# Frequency_synthesizer_v1_1.net
KiCad netlist of a schematic drawn in EAGLE
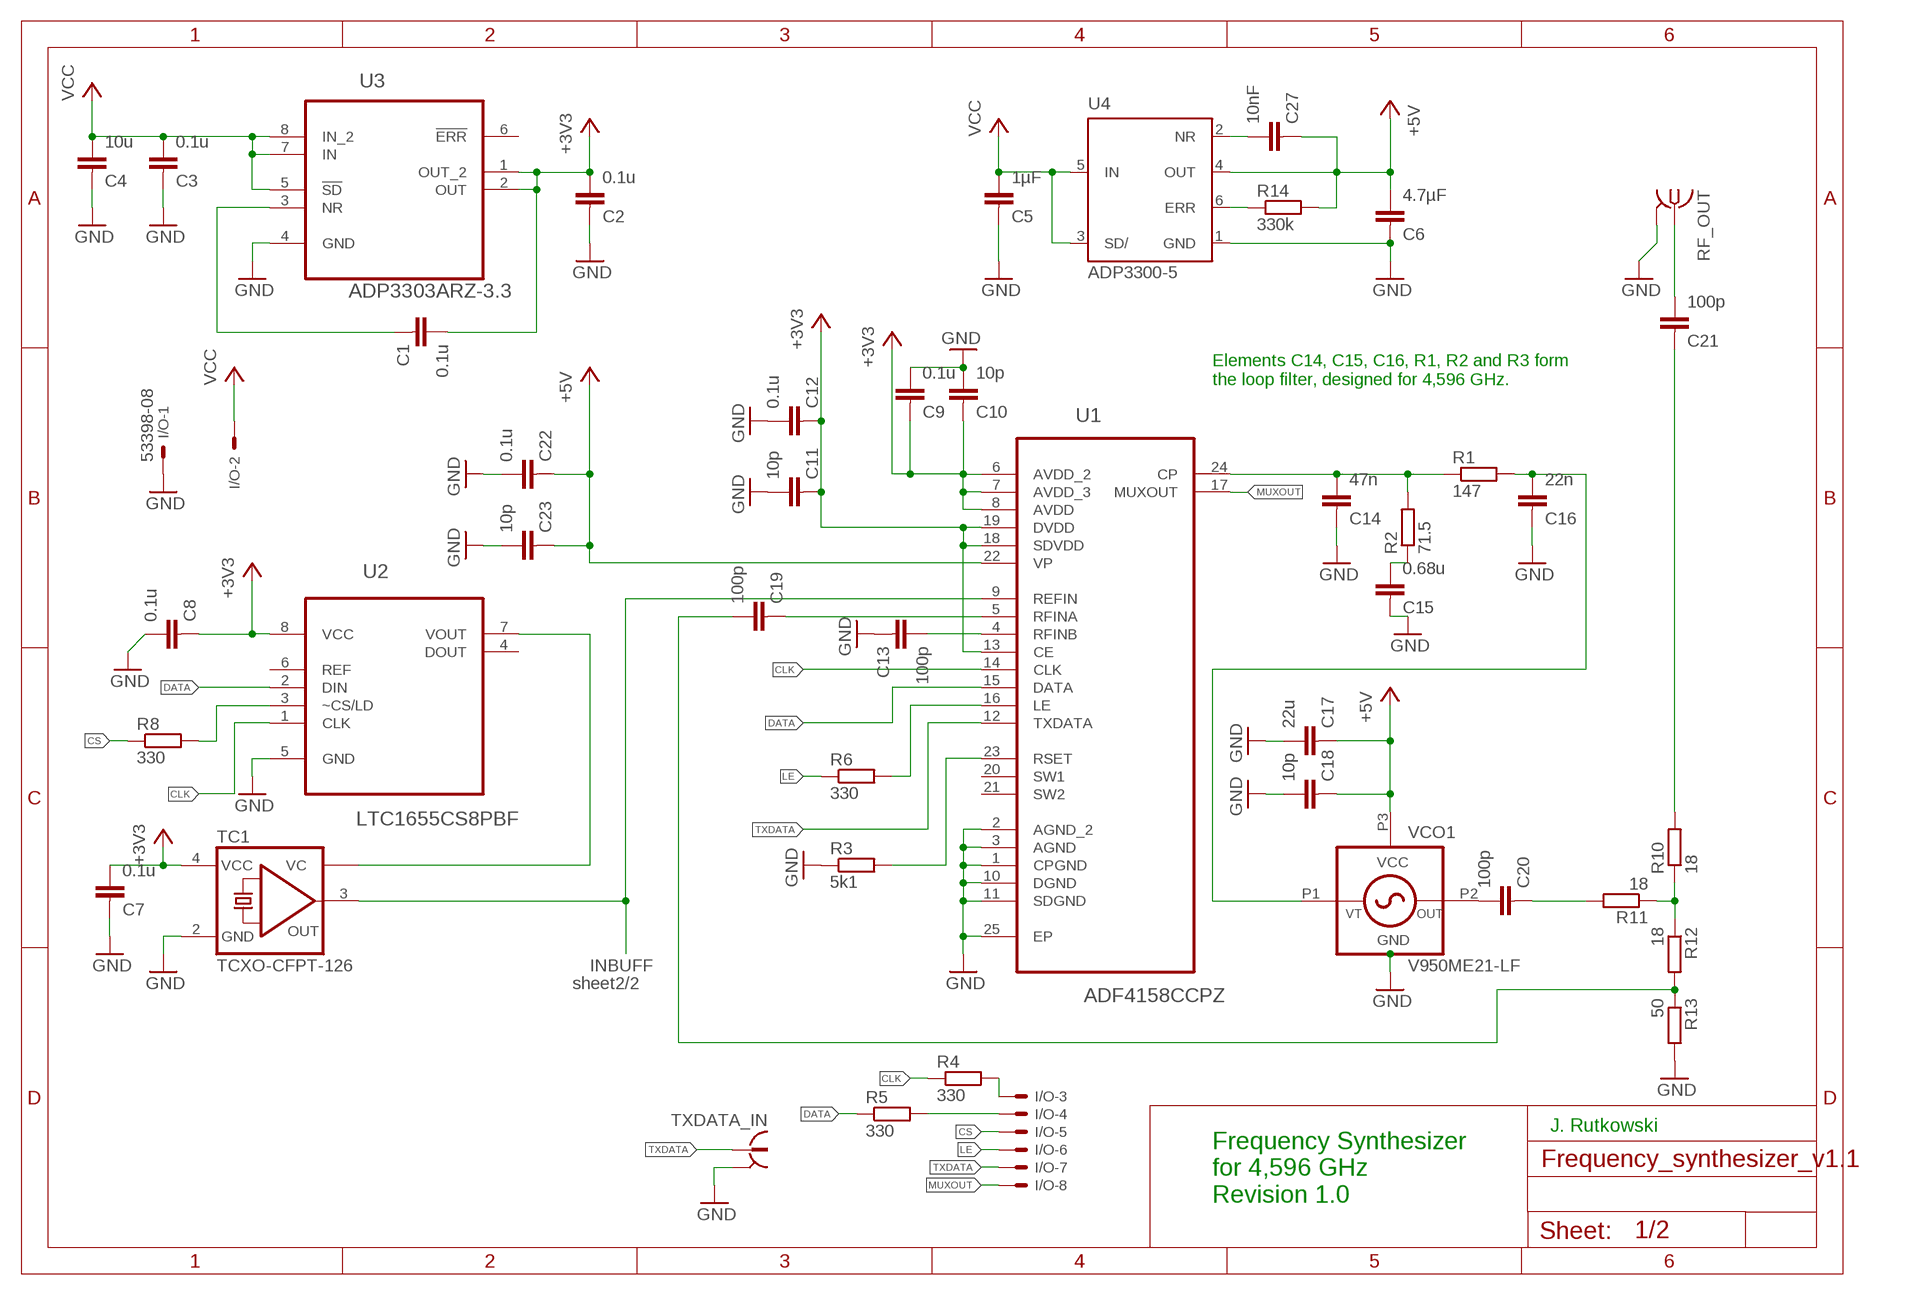
[diagram p0: schematic, sheet 1]
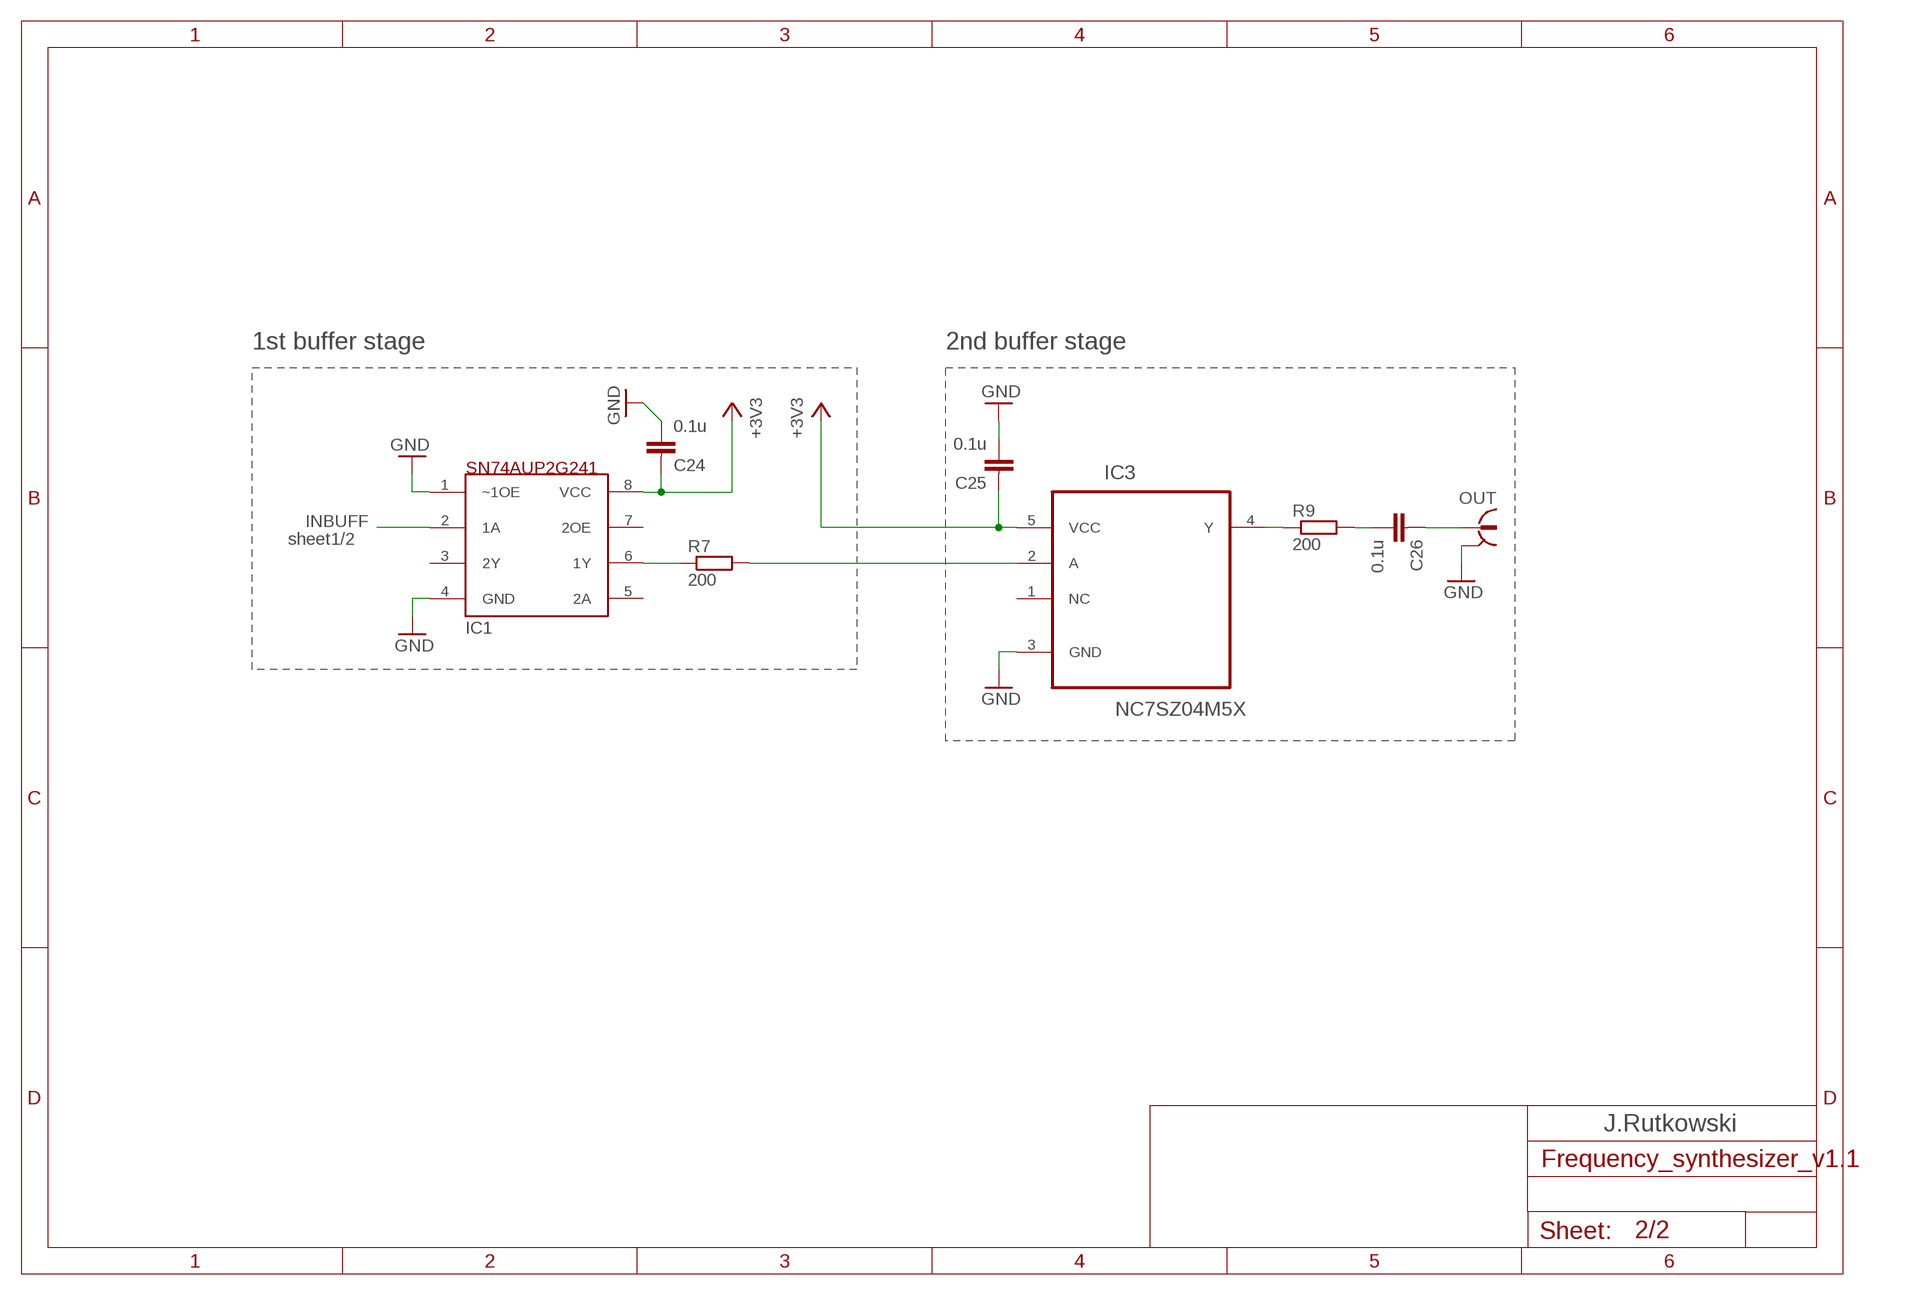
[diagram p1: schematic, sheet 2]

(export (version "E")
  (design (tool "Eeschema 10.0.6"))
  (components
    (comp (ref "C1")
      (value "0.1u")
      (footprint "eagle-import:C0603K")
      (libsource (lib "eagle-import") (part "C-EUC0603K"))
    )
    (comp (ref "C2")
      (value "0.1u")
      (footprint "eagle-import:C0603K")
      (libsource (lib "eagle-import") (part "C-EUC0603K"))
    )
    (comp (ref "C3")
      (value "0.1u")
      (footprint "eagle-import:C0603K")
      (libsource (lib "eagle-import") (part "C-EUC0603K"))
    )
    (comp (ref "C4")
      (value "10u")
      (footprint "eagle-import:C0805K")
      (libsource (lib "eagle-import") (part "C-EUC0805K"))
    )
    (comp (ref "C5")
      (value "1µF")
      (footprint "eagle-import:C0603K")
      (libsource (lib "eagle-import") (part "C-EUC0603K"))
    )
    (comp (ref "C6")
      (value "4.7µF")
      (footprint "eagle-import:C0603K")
      (libsource (lib "eagle-import") (part "C-EUC0603K"))
    )
    (comp (ref "C7")
      (value "0.1u")
      (footprint "eagle-import:C0603K")
      (libsource (lib "eagle-import") (part "C-EUC0603K"))
    )
    (comp (ref "C8")
      (value "0.1u")
      (footprint "eagle-import:C0603K")
      (libsource (lib "eagle-import") (part "C-EUC0603K"))
    )
    (comp (ref "C9")
      (value "0.1u")
      (footprint "eagle-import:C0603K")
      (libsource (lib "eagle-import") (part "C-EUC0603K"))
    )
    (comp (ref "C10")
      (value "10p")
      (footprint "eagle-import:C0603K")
      (libsource (lib "eagle-import") (part "C-EUC0603K"))
    )
    (comp (ref "C11")
      (value "10p")
      (footprint "eagle-import:C0603K")
      (libsource (lib "eagle-import") (part "C-EUC0603K"))
    )
    (comp (ref "C12")
      (value "0.1u")
      (footprint "eagle-import:C0603K")
      (libsource (lib "eagle-import") (part "C-EUC0603K"))
    )
    (comp (ref "C13")
      (value "100p")
      (footprint "eagle-import:C0402")
      (libsource (lib "eagle-import") (part "C-EUC0402"))
    )
    (comp (ref "C14")
      (value "47n")
      (footprint "eagle-import:C0603K")
      (libsource (lib "eagle-import") (part "C-EUC0603K"))
    )
    (comp (ref "C15")
      (value "0.68u")
      (footprint "eagle-import:C0603K")
      (libsource (lib "eagle-import") (part "C-EUC0603K"))
    )
    (comp (ref "C16")
      (value "22n")
      (footprint "eagle-import:C0603K")
      (libsource (lib "eagle-import") (part "C-EUC0603K"))
    )
    (comp (ref "C17")
      (value "22u")
      (footprint "eagle-import:C0805")
      (libsource (lib "eagle-import") (part "C-EUC0805"))
    )
    (comp (ref "C18")
      (value "10p")
      (footprint "eagle-import:C0603K")
      (libsource (lib "eagle-import") (part "C-EUC0603K"))
    )
    (comp (ref "C19")
      (value "100p")
      (footprint "eagle-import:C0402")
      (libsource (lib "eagle-import") (part "C-EUC0402"))
    )
    (comp (ref "C20")
      (value "100p")
      (footprint "eagle-import:C0402")
      (libsource (lib "eagle-import") (part "C-EUC0402"))
    )
    (comp (ref "C21")
      (value "100p")
      (footprint "eagle-import:C0402")
      (libsource (lib "eagle-import") (part "C-EUC0402"))
    )
    (comp (ref "C22")
      (value "0.1u")
      (footprint "eagle-import:C0603K")
      (libsource (lib "eagle-import") (part "C-EUC0603K"))
    )
    (comp (ref "C23")
      (value "10p")
      (footprint "eagle-import:C0603K")
      (libsource (lib "eagle-import") (part "C-EUC0603K"))
    )
    (comp (ref "C27")
      (value "10nF")
      (footprint "eagle-import:C0603K")
      (libsource (lib "eagle-import") (part "C-EUC0603K"))
    )
    (comp (ref "I/O")
      (value "53398-08")
      (footprint "eagle-import:53398-08")
      (libsource (lib "eagle-import") (part "53?-08398"))
    )
    (comp (ref "R1")
      (value "147")
      (footprint "eagle-import:R0603")
      (libsource (lib "eagle-import") (part "R-EU_R0603"))
    )
    (comp (ref "R2")
      (value "71.5")
      (footprint "eagle-import:R0603")
      (libsource (lib "eagle-import") (part "R-EU_R0603"))
    )
    (comp (ref "R3")
      (value "5k1")
      (footprint "eagle-import:R0603")
      (libsource (lib "eagle-import") (part "R-EU_R0603"))
    )
    (comp (ref "R4")
      (value "330")
      (footprint "eagle-import:R0603")
      (libsource (lib "eagle-import") (part "R-EU_R0603"))
    )
    (comp (ref "R5")
      (value "330")
      (footprint "eagle-import:R0603")
      (libsource (lib "eagle-import") (part "R-EU_R0603"))
    )
    (comp (ref "R6")
      (value "330")
      (footprint "eagle-import:R0603")
      (libsource (lib "eagle-import") (part "R-EU_R0603"))
    )
    (comp (ref "R8")
      (value "330")
      (footprint "eagle-import:R0603")
      (libsource (lib "eagle-import") (part "R-EU_R0603"))
    )
    (comp (ref "R10")
      (value "18")
      (footprint "eagle-import:R0402")
      (libsource (lib "eagle-import") (part "R-EU_R0402"))
    )
    (comp (ref "R11")
      (value "18")
      (footprint "eagle-import:R0402")
      (libsource (lib "eagle-import") (part "R-EU_R0402"))
    )
    (comp (ref "R12")
      (value "18")
      (footprint "eagle-import:R0402")
      (libsource (lib "eagle-import") (part "R-EU_R0402"))
    )
    (comp (ref "R13")
      (value "50")
      (footprint "eagle-import:R0402")
      (libsource (lib "eagle-import") (part "R-EU_R0402"))
    )
    (comp (ref "R14")
      (value "330k")
      (footprint "eagle-import:R0603")
      (libsource (lib "eagle-import") (part "R-EU_R0603"))
    )
    (comp (ref "RF_OUT")
      (value "SMA-142-0711-871/876")
      (footprint "eagle-import:J502-ND-142-0711-871_876")
      (fields (field (name "MF") "JOHNSON COMPONENTS") (field (name "MPN") "142-0711-871"))
      (libsource (lib "eagle-import") (part "SMA-142-0711-871/876"))
    )
    (comp (ref "TC1")
      (value "TCXO-CFPT-126")
      (footprint "eagle-import:7.0X5.0-4-PAD")
      (libsource (lib "eagle-import") (part "TCXO-CFPT-126"))
    )
    (comp (ref "TXDATA_IN")
      (value "734120110")
      (footprint "eagle-import:734120110")
      (libsource (lib "eagle-import") (part "734120110"))
    )
    (comp (ref "U1")
      (value "ADF4158CCPZ")
      (footprint "eagle-import:QFN50P400X400X80-25N")
      (libsource (lib "eagle-import") (part "ADF4158CCPZ"))
    )
    (comp (ref "U2")
      (value "LTC1655CS8PBF")
      (footprint "eagle-import:SOIC127P600X175-8N")
      (fields (field (name "MPN") "LTC1655CS8#PBF"))
      (libsource (lib "eagle-import") (part "LTC1655CS8PBF"))
    )
    (comp (ref "U3")
      (value "ADP3303ARZ-3.3")
      (footprint "eagle-import:SOIC127P600X175-8N")
      (libsource (lib "eagle-import") (part "ADP3303ARZ-3.3"))
    )
    (comp (ref "U4")
      (value "ADP3300-5")
      (footprint "eagle-import:SOT23-6")
      (libsource (lib "eagle-import") (part "ADP3300-5"))
    )
    (comp (ref "VCO1")
      (value "V950ME21-LF")
      (footprint "eagle-import:MINI-14S")
      (libsource (lib "eagle-import") (part "MINI-14S"))
    )
    (comp (ref "C24")
      (value "0.1u")
      (footprint "eagle-import:C0603K")
      (libsource (lib "eagle-import") (part "C-EUC0603K"))
    )
    (comp (ref "C25")
      (value "0.1u")
      (footprint "eagle-import:C0603K")
      (libsource (lib "eagle-import") (part "C-EUC0603K"))
    )
    (comp (ref "C26")
      (value "0.1u")
      (footprint "eagle-import:C0603K")
      (libsource (lib "eagle-import") (part "C-EUC0603K"))
    )
    (comp (ref "IC1")
      (value "SN74AUP2G241")
      (footprint "eagle-import:DCU_(R-PDSO-G8)")
      (libsource (lib "eagle-import") (part "SN74AUP2G241"))
    )
    (comp (ref "IC3")
      (value "NC7SZ04M5X")
      (footprint "eagle-import:SOT95P280X145-5N")
      (libsource (lib "eagle-import") (part "NC7SZ04M5X"))
    )
    (comp (ref "OUT")
      (value "734120110")
      (footprint "eagle-import:734120110")
      (libsource (lib "eagle-import") (part "734120110"))
    )
    (comp (ref "R7")
      (value "200")
      (footprint "eagle-import:R0603")
      (libsource (lib "eagle-import") (part "R-EU_R0603"))
    )
    (comp (ref "R9")
      (value "200")
      (footprint "eagle-import:R0603")
      (libsource (lib "eagle-import") (part "R-EU_R0603"))
    )
  )
  (nets
    (net (code "1") (name "+3V3") (class "Default")
      (node (ref "C1") (pin "1") (pinfunction "1_1") (pintype "passive"))
      (node (ref "C10") (pin "2") (pinfunction "2_2") (pintype "passive"))
      (node (ref "C11") (pin "2") (pinfunction "2_2") (pintype "passive"))
      (node (ref "C12") (pin "2") (pinfunction "2_2") (pintype "passive"))
      (node (ref "C2") (pin "1") (pinfunction "1_1") (pintype "passive"))
      (node (ref "C24") (pin "2") (pinfunction "2_2") (pintype "passive"))
      (node (ref "C25") (pin "2") (pinfunction "2_2") (pintype "passive"))
      (node (ref "C7") (pin "1") (pinfunction "1_1") (pintype "passive"))
      (node (ref "C8") (pin "2") (pinfunction "2_2") (pintype "passive"))
      (node (ref "C9") (pin "2") (pinfunction "2_2") (pintype "passive"))
      (node (ref "IC1") (pin "8") (pinfunction "VCC_8") (pintype "bidirectional"))
      (node (ref "IC3") (pin "5") (pinfunction "VCC_5") (pintype "power_in"))
      (node (ref "TC1") (pin "4") (pinfunction "VCC_4") (pintype "power_in"))
      (node (ref "U1") (pin "13") (pinfunction "CE_13") (pintype "input"))
      (node (ref "U1") (pin "18") (pinfunction "SDVDD_18") (pintype "power_in"))
      (node (ref "U1") (pin "19") (pinfunction "DVDD_19") (pintype "power_in"))
      (node (ref "U1") (pin "6") (pinfunction "AVDD_2_6") (pintype "power_in"))
      (node (ref "U1") (pin "7") (pinfunction "AVDD_3_7") (pintype "power_in"))
      (node (ref "U1") (pin "8") (pinfunction "AVDD_8") (pintype "power_in"))
      (node (ref "U2") (pin "8") (pinfunction "VCC_8") (pintype "power_in"))
      (node (ref "U3") (pin "1") (pinfunction "OUT_2_1") (pintype "output"))
      (node (ref "U3") (pin "2") (pinfunction "OUT_2") (pintype "output"))
    )
    (net (code "2") (name "+5V") (class "Default")
      (node (ref "C17") (pin "2") (pinfunction "2_2") (pintype "passive"))
      (node (ref "C18") (pin "2") (pinfunction "2_2") (pintype "passive"))
      (node (ref "C22") (pin "2") (pinfunction "2_2") (pintype "passive"))
      (node (ref "C23") (pin "2") (pinfunction "2_2") (pintype "passive"))
      (node (ref "C27") (pin "2") (pinfunction "2_2") (pintype "passive"))
      (node (ref "C6") (pin "1") (pinfunction "1_1") (pintype "passive"))
      (node (ref "R14") (pin "2") (pinfunction "2_2") (pintype "passive"))
      (node (ref "U1") (pin "22") (pinfunction "VP_22") (pintype "power_in"))
      (node (ref "U4") (pin "4") (pinfunction "OUT_4") (pintype "output"))
      (node (ref "VCO1") (pin "P3") (pinfunction "VCC_P3") (pintype "power_in"))
    )
    (net (code "3") (name "CLK") (class "Default")
      (node (ref "R4") (pin "1") (pinfunction "1_1") (pintype "passive"))
      (node (ref "U1") (pin "14") (pinfunction "CLK_14") (pintype "input"))
      (node (ref "U2") (pin "1") (pinfunction "CLK_1") (pintype "input"))
    )
    (net (code "4") (name "CS") (class "Default")
      (node (ref "I/O") (pin "5") (pinfunction "S_5") (pintype "passive"))
      (node (ref "R8") (pin "1") (pinfunction "1_1") (pintype "passive"))
    )
    (net (code "5") (name "DATA") (class "Default")
      (node (ref "R5") (pin "1") (pinfunction "1_1") (pintype "passive"))
      (node (ref "U1") (pin "15") (pinfunction "DATA_15") (pintype "input"))
      (node (ref "U2") (pin "2") (pinfunction "DIN_2") (pintype "input"))
    )
    (net (code "6") (name "GND") (class "Default")
      (node (ref "C10") (pin "1") (pinfunction "1_1") (pintype "passive"))
      (node (ref "C11") (pin "1") (pinfunction "1_1") (pintype "passive"))
      (node (ref "C12") (pin "1") (pinfunction "1_1") (pintype "passive"))
      (node (ref "C13") (pin "2") (pinfunction "2_2") (pintype "passive"))
      (node (ref "C14") (pin "2") (pinfunction "2_2") (pintype "passive"))
      (node (ref "C15") (pin "2") (pinfunction "2_2") (pintype "passive"))
      (node (ref "C16") (pin "2") (pinfunction "2_2") (pintype "passive"))
      (node (ref "C17") (pin "1") (pinfunction "1_1") (pintype "passive"))
      (node (ref "C18") (pin "1") (pinfunction "1_1") (pintype "passive"))
      (node (ref "C2") (pin "2") (pinfunction "2_2") (pintype "passive"))
      (node (ref "C22") (pin "1") (pinfunction "1_1") (pintype "passive"))
      (node (ref "C23") (pin "1") (pinfunction "1_1") (pintype "passive"))
      (node (ref "C24") (pin "1") (pinfunction "1_1") (pintype "passive"))
      (node (ref "C25") (pin "1") (pinfunction "1_1") (pintype "passive"))
      (node (ref "C3") (pin "2") (pinfunction "2_2") (pintype "passive"))
      (node (ref "C4") (pin "2") (pinfunction "2_2") (pintype "passive"))
      (node (ref "C5") (pin "2") (pinfunction "2_2") (pintype "passive"))
      (node (ref "C6") (pin "2") (pinfunction "2_2") (pintype "passive"))
      (node (ref "C7") (pin "2") (pinfunction "2_2") (pintype "passive"))
      (node (ref "C8") (pin "1") (pinfunction "1_1") (pintype "passive"))
      (node (ref "C9") (pin "1") (pinfunction "1_1") (pintype "passive"))
      (node (ref "I/O") (pin "1") (pinfunction "S_1") (pintype "passive"))
      (node (ref "IC1") (pin "1") (pinfunction "~{1OE}_1") (pintype "bidirectional"))
      (node (ref "IC1") (pin "4") (pinfunction "GND_4") (pintype "bidirectional"))
      (node (ref "IC3") (pin "3") (pinfunction "GND_3") (pintype "passive"))
      (node (ref "OUT") (pin "S@1") (pinfunction "2_S@1") (pintype "passive"))
      (node (ref "OUT") (pin "S@2") (pinfunction "2_S@2") (pintype "passive"))
      (node (ref "OUT") (pin "S@3") (pinfunction "2_S@3") (pintype "passive"))
      (node (ref "R13") (pin "2") (pinfunction "2_2") (pintype "passive"))
      (node (ref "R3") (pin "1") (pinfunction "1_1") (pintype "passive"))
      (node (ref "RF_OUT") (pin "G@1") (pinfunction "2_G@1") (pintype "passive"))
      (node (ref "RF_OUT") (pin "G@2") (pinfunction "2_G@2") (pintype "passive"))
      (node (ref "RF_OUT") (pin "G@3") (pinfunction "2_G@3") (pintype "passive"))
      (node (ref "RF_OUT") (pin "G@4") (pinfunction "2_G@4") (pintype "passive"))
      (node (ref "TC1") (pin "2") (pinfunction "GND_2") (pintype "power_in"))
      (node (ref "TXDATA_IN") (pin "S@1") (pinfunction "2_S@1") (pintype "passive"))
      (node (ref "TXDATA_IN") (pin "S@2") (pinfunction "2_S@2") (pintype "passive"))
      (node (ref "TXDATA_IN") (pin "S@3") (pinfunction "2_S@3") (pintype "passive"))
      (node (ref "U1") (pin "1") (pinfunction "CPGND_1") (pintype "passive"))
      (node (ref "U1") (pin "10") (pinfunction "DGND_10") (pintype "passive"))
      (node (ref "U1") (pin "11") (pinfunction "SDGND_11") (pintype "passive"))
      (node (ref "U1") (pin "2") (pinfunction "AGND_2_2") (pintype "passive"))
      (node (ref "U1") (pin "25") (pinfunction "EP_25") (pintype "passive"))
      (node (ref "U1") (pin "3") (pinfunction "AGND_3") (pintype "passive"))
      (node (ref "U2") (pin "5") (pinfunction "GND_5") (pintype "passive"))
      (node (ref "U3") (pin "4") (pinfunction "GND_4") (pintype "passive"))
      (node (ref "U4") (pin "1") (pinfunction "GND_1") (pintype "power_in"))
      (node (ref "VCO1") (pin "S1") (pinfunction "S1_S1") (pintype "power_in"))
      (node (ref "VCO1") (pin "S10") (pinfunction "S10_S10") (pintype "power_in"))
      (node (ref "VCO1") (pin "S11") (pinfunction "S11_S11") (pintype "power_in"))
      (node (ref "VCO1") (pin "S2") (pinfunction "S2_S2") (pintype "power_in"))
      (node (ref "VCO1") (pin "S3") (pinfunction "S3_S3") (pintype "power_in"))
      (node (ref "VCO1") (pin "S4") (pinfunction "S4_S4") (pintype "power_in"))
      (node (ref "VCO1") (pin "S5") (pinfunction "S5_S5") (pintype "power_in"))
      (node (ref "VCO1") (pin "S6") (pinfunction "S6_S6") (pintype "power_in"))
      (node (ref "VCO1") (pin "S7") (pinfunction "S7_S7") (pintype "power_in"))
      (node (ref "VCO1") (pin "S8") (pinfunction "S8_S8") (pintype "power_in"))
      (node (ref "VCO1") (pin "S9") (pinfunction "S9_S9") (pintype "power_in"))
    )
    (net (code "7") (name "INBUFF") (class "Default")
      (node (ref "IC1") (pin "2") (pinfunction "1A_2") (pintype "bidirectional"))
      (node (ref "TC1") (pin "3") (pinfunction "OUT_3") (pintype "output"))
      (node (ref "U1") (pin "9") (pinfunction "REFIN_9") (pintype "input"))
    )
    (net (code "8") (name "LE") (class "Default")
      (node (ref "I/O") (pin "6") (pinfunction "S_6") (pintype "passive"))
      (node (ref "R6") (pin "1") (pinfunction "1_1") (pintype "passive"))
    )
    (net (code "9") (name "MUXOUT") (class "Default")
      (node (ref "I/O") (pin "8") (pinfunction "S_8") (pintype "passive"))
      (node (ref "U1") (pin "17") (pinfunction "MUXOUT_17") (pintype "output"))
    )
    (net (code "10") (name "Net-(C15-Pad1)") (class "Default")
      (node (ref "C15") (pin "1") (pinfunction "1_1") (pintype "passive"))
      (node (ref "R2") (pin "1") (pinfunction "1_1") (pintype "passive"))
    )
    (net (code "11") (name "Net-(C19-Pad1)") (class "Default")
      (node (ref "C19") (pin "1") (pinfunction "1_1") (pintype "passive"))
      (node (ref "R12") (pin "2") (pinfunction "2_2") (pintype "passive"))
      (node (ref "R13") (pin "1") (pinfunction "1_1") (pintype "passive"))
    )
    (net (code "12") (name "Net-(C20-Pad2)") (class "Default")
      (node (ref "C20") (pin "2") (pinfunction "2_2") (pintype "passive"))
      (node (ref "R11") (pin "2") (pinfunction "2_2") (pintype "passive"))
    )
    (net (code "13") (name "Net-(C21-Pad1)") (class "Default")
      (node (ref "C21") (pin "1") (pinfunction "1_1") (pintype "passive"))
      (node (ref "RF_OUT") (pin "1") (pinfunction "1_1") (pintype "passive"))
    )
    (net (code "14") (name "Net-(C21-Pad2)") (class "Default")
      (node (ref "C21") (pin "2") (pinfunction "2_2") (pintype "passive"))
      (node (ref "R10") (pin "2") (pinfunction "2_2") (pintype "passive"))
    )
    (net (code "15") (name "Net-(C26-Pad1)") (class "Default")
      (node (ref "C26") (pin "1") (pinfunction "1_1") (pintype "passive"))
      (node (ref "R9") (pin "2") (pinfunction "2_2") (pintype "passive"))
    )
    (net (code "16") (name "Net-(C26-Pad2)") (class "Default")
      (node (ref "C26") (pin "2") (pinfunction "2_2") (pintype "passive"))
      (node (ref "OUT") (pin "1") (pinfunction "1_1") (pintype "passive"))
    )
    (net (code "17") (name "Net-(I/OC-S)") (class "Default")
      (node (ref "I/O") (pin "3") (pinfunction "S_3") (pintype "passive"))
      (node (ref "R4") (pin "2") (pinfunction "2_2") (pintype "passive"))
    )
    (net (code "18") (name "Net-(I/OD-S)") (class "Default")
      (node (ref "I/O") (pin "4") (pinfunction "S_4") (pintype "passive"))
      (node (ref "R5") (pin "2") (pinfunction "2_2") (pintype "passive"))
    )
    (net (code "19") (name "Net-(IC1-1Y)") (class "Default")
      (node (ref "IC1") (pin "6") (pinfunction "1Y_6") (pintype "bidirectional"))
      (node (ref "R7") (pin "1") (pinfunction "1_1") (pintype "passive"))
    )
    (net (code "20") (name "Net-(IC3-A)") (class "Default")
      (node (ref "IC3") (pin "2") (pinfunction "A_2") (pintype "input"))
      (node (ref "R7") (pin "2") (pinfunction "2_2") (pintype "passive"))
    )
    (net (code "21") (name "Net-(IC3-Y)") (class "Default")
      (node (ref "IC3") (pin "4") (pinfunction "Y_4") (pintype "output"))
      (node (ref "R9") (pin "1") (pinfunction "1_1") (pintype "passive"))
    )
    (net (code "22") (name "Net-(R10-Pad1)") (class "Default")
      (node (ref "R10") (pin "1") (pinfunction "1_1") (pintype "passive"))
      (node (ref "R11") (pin "1") (pinfunction "1_1") (pintype "passive"))
      (node (ref "R12") (pin "1") (pinfunction "1_1") (pintype "passive"))
    )
    (net (code "23") (name "Net-(TC1-VC)") (class "Default")
      (node (ref "TC1") (pin "1") (pinfunction "VC_1") (pintype "input"))
      (node (ref "U2") (pin "7") (pinfunction "VOUT_7") (pintype "output"))
    )
    (net (code "24") (name "Net-(U1-CP)") (class "Default")
      (node (ref "C14") (pin "1") (pinfunction "1_1") (pintype "passive"))
      (node (ref "R1") (pin "1") (pinfunction "1_1") (pintype "passive"))
      (node (ref "R2") (pin "2") (pinfunction "2_2") (pintype "passive"))
      (node (ref "U1") (pin "24") (pinfunction "CP_24") (pintype "output"))
    )
    (net (code "25") (name "Net-(U1-LE)") (class "Default")
      (node (ref "R6") (pin "2") (pinfunction "2_2") (pintype "passive"))
      (node (ref "U1") (pin "16") (pinfunction "LE_16") (pintype "input"))
    )
    (net (code "26") (name "Net-(U1-RFINA)") (class "Default")
      (node (ref "C19") (pin "2") (pinfunction "2_2") (pintype "passive"))
      (node (ref "U1") (pin "5") (pinfunction "RFINA_5") (pintype "input"))
    )
    (net (code "27") (name "Net-(U1-RFINB)") (class "Default")
      (node (ref "C13") (pin "1") (pinfunction "1_1") (pintype "passive"))
      (node (ref "U1") (pin "4") (pinfunction "RFINB_4") (pintype "input"))
    )
    (net (code "28") (name "Net-(U1-RSET)") (class "Default")
      (node (ref "R3") (pin "2") (pinfunction "2_2") (pintype "passive"))
      (node (ref "U1") (pin "23") (pinfunction "RSET_23") (pintype "passive"))
    )
    (net (code "29") (name "Net-(U2-~{CS{slash}LD})") (class "Default")
      (node (ref "R8") (pin "2") (pinfunction "2_2") (pintype "passive"))
      (node (ref "U2") (pin "3") (pinfunction "~{CS/LD}_3") (pintype "input"))
    )
    (net (code "30") (name "Net-(U3-NR)") (class "Default")
      (node (ref "C1") (pin "2") (pinfunction "2_2") (pintype "passive"))
      (node (ref "U3") (pin "3") (pinfunction "NR_3") (pintype "input"))
    )
    (net (code "31") (name "Net-(U4-ERR)") (class "Default")
      (node (ref "R14") (pin "1") (pinfunction "1_1") (pintype "passive"))
      (node (ref "U4") (pin "6") (pinfunction "ERR_6") (pintype "output"))
    )
    (net (code "32") (name "Net-(U4-NR)") (class "Default")
      (node (ref "C27") (pin "1") (pinfunction "1_1") (pintype "passive"))
      (node (ref "U4") (pin "2") (pinfunction "NR_2") (pintype "output"))
    )
    (net (code "33") (name "Net-(VCO1-OUT)") (class "Default")
      (node (ref "C20") (pin "1") (pinfunction "1_1") (pintype "passive"))
      (node (ref "VCO1") (pin "P2") (pinfunction "OUT_P2") (pintype "output"))
    )
    (net (code "34") (name "Net-(VCO1-VT)") (class "Default")
      (node (ref "C16") (pin "1") (pinfunction "1_1") (pintype "passive"))
      (node (ref "R1") (pin "2") (pinfunction "2_2") (pintype "passive"))
      (node (ref "VCO1") (pin "P1") (pinfunction "VT_P1") (pintype "input"))
    )
    (net (code "35") (name "TXDATA") (class "Default")
      (node (ref "I/O") (pin "7") (pinfunction "S_7") (pintype "passive"))
      (node (ref "TXDATA_IN") (pin "1") (pinfunction "1_1") (pintype "passive"))
      (node (ref "U1") (pin "12") (pinfunction "TXDATA_12") (pintype "input"))
    )
    (net (code "36") (name "VCC") (class "Default")
      (node (ref "C3") (pin "1") (pinfunction "1_1") (pintype "passive"))
      (node (ref "C4") (pin "1") (pinfunction "1_1") (pintype "passive"))
      (node (ref "C5") (pin "1") (pinfunction "1_1") (pintype "passive"))
      (node (ref "I/O") (pin "2") (pinfunction "S_2") (pintype "passive"))
      (node (ref "U3") (pin "5") (pinfunction "~{SD}_5") (pintype "input"))
      (node (ref "U3") (pin "7") (pinfunction "IN_7") (pintype "input"))
      (node (ref "U3") (pin "8") (pinfunction "IN_2_8") (pintype "input"))
      (node (ref "U4") (pin "3") (pinfunction "SD/_3") (pintype "bidirectional"))
      (node (ref "U4") (pin "5") (pinfunction "IN_5") (pintype "input"))
    )
    (net (code "37") (name "unconnected-(IC1-2A-Pad5)") (class "Default")
      (node (ref "IC1") (pin "5") (pinfunction "2A_5") (pintype "bidirectional"))
    )
    (net (code "38") (name "unconnected-(IC1-2OE-Pad7)") (class "Default")
      (node (ref "IC1") (pin "7") (pinfunction "2OE_7") (pintype "bidirectional"))
    )
    (net (code "39") (name "unconnected-(IC1-2Y-Pad3)") (class "Default")
      (node (ref "IC1") (pin "3") (pinfunction "2Y_3") (pintype "bidirectional"))
    )
    (net (code "40") (name "unconnected-(IC3-NC-Pad1)") (class "Default")
      (node (ref "IC3") (pin "1") (pinfunction "NC_1") (pintype "no_connect"))
    )
    (net (code "41") (name "unconnected-(U1-SW1-Pad20)") (class "Default")
      (node (ref "U1") (pin "20") (pinfunction "SW1_20") (pintype "passive"))
    )
    (net (code "42") (name "unconnected-(U1-SW2-Pad21)") (class "Default")
      (node (ref "U1") (pin "21") (pinfunction "SW2_21") (pintype "passive"))
    )
    (net (code "43") (name "unconnected-(U2-DOUT-Pad4)") (class "Default")
      (node (ref "U2") (pin "4") (pinfunction "DOUT_4") (pintype "output"))
    )
    (net (code "44") (name "unconnected-(U2-REF-Pad6)") (class "Default")
      (node (ref "U2") (pin "6") (pinfunction "REF_6") (pintype "input"))
    )
    (net (code "45") (name "unconnected-(U3-~{ERR}-Pad6)") (class "Default")
      (node (ref "U3") (pin "6") (pinfunction "~{ERR}_6") (pintype "output"))
    )
  )
)
